# Horizontally_Mounted_Lighthouse_V16.net
KiCad netlist of a schematic drawn in EAGLE
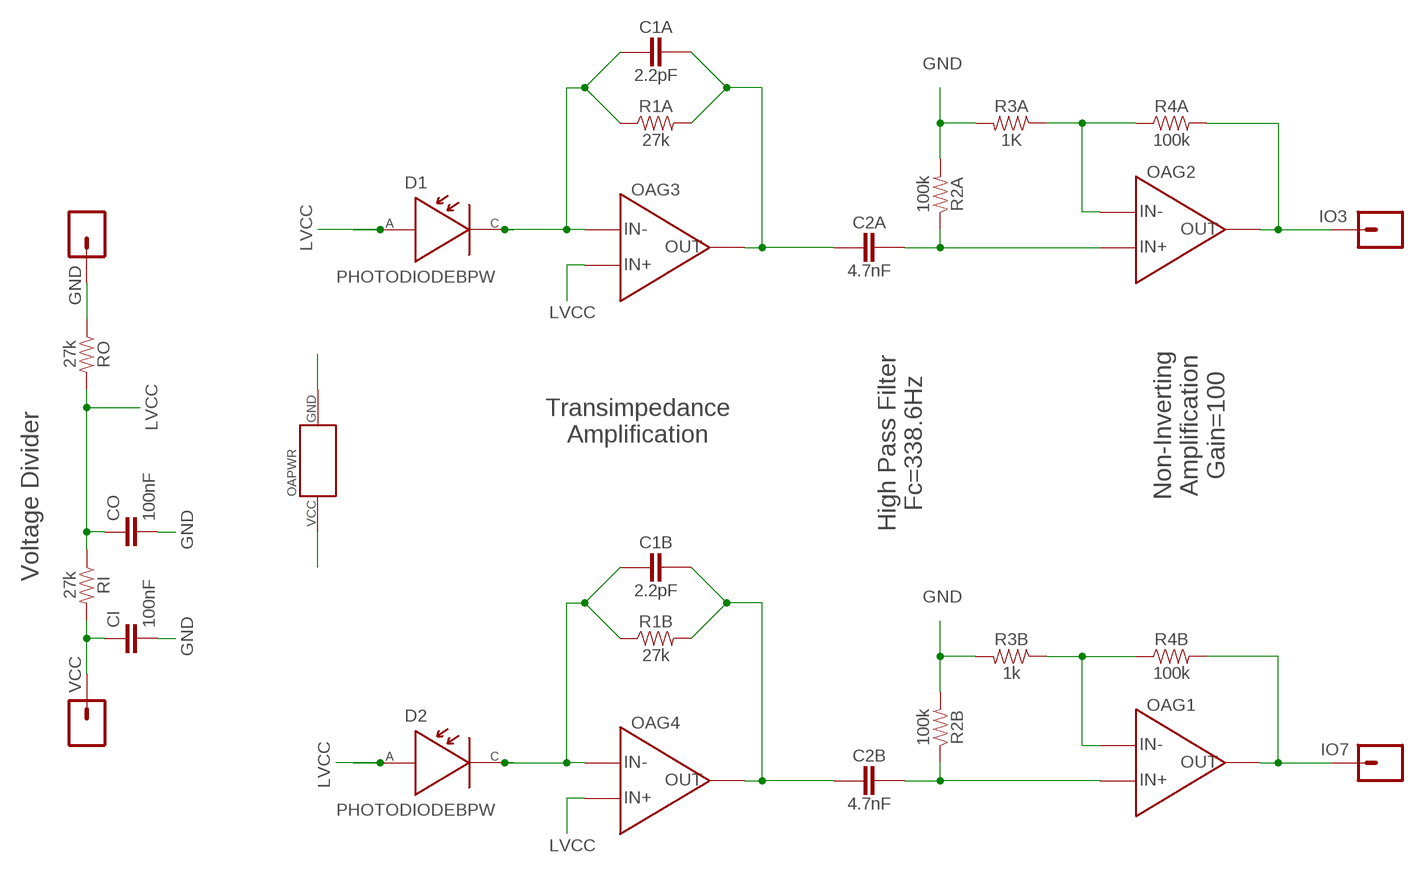
[diagram p0: schematic, sheet 1]

(export (version "E")
  (design (tool "Eeschema 10.0.6"))
  (components
    (comp (ref "C1A")
      (value "2.2pF")
      (footprint "eagle-import:PASSIVE-0603")
      (libsource (lib "eagle-import") (part "CAPACITOR"))
    )
    (comp (ref "C1B")
      (value "2.2pF")
      (footprint "eagle-import:PASSIVE-0603")
      (libsource (lib "eagle-import") (part "CAPACITOR"))
    )
    (comp (ref "C2A")
      (value "4.7nF")
      (footprint "eagle-import:PASSIVE-0603")
      (libsource (lib "eagle-import") (part "CAPACITOR"))
    )
    (comp (ref "C2B")
      (value "4.7nF")
      (footprint "eagle-import:PASSIVE-0603")
      (libsource (lib "eagle-import") (part "CAPACITOR"))
    )
    (comp (ref "CI")
      (value "100nF")
      (footprint "eagle-import:0603")
      (libsource (lib "eagle-import") (part "4.7PF-0603-50V-5%"))
    )
    (comp (ref "CO")
      (value "100nF")
      (footprint "eagle-import:0603")
      (libsource (lib "eagle-import") (part "4.7PF-0603-50V-5%"))
    )
    (comp (ref "D1")
      (value "PHOTODIODEBPW")
      (footprint "eagle-import:BPW34_BP104_SMD")
      (libsource (lib "eagle-import") (part "PHOTODIODEBPW"))
    )
    (comp (ref "D2")
      (value "PHOTODIODEBPW")
      (footprint "eagle-import:BPW34_BP104_SMD")
      (libsource (lib "eagle-import") (part "PHOTODIODEBPW"))
    )
    (comp (ref "GND")
      (value "CONN_01PTH_NO_SILK_YES_STOP")
      (footprint "eagle-import:1X01_NO_SILK")
      (libsource (lib "eagle-import") (part "CONN_01PTH_NO_SILK_YES_STOP"))
    )
    (comp (ref "IO3")
      (value "CONN_01PTH_NO_SILK_YES_STOP")
      (footprint "eagle-import:1X01_NO_SILK")
      (libsource (lib "eagle-import") (part "CONN_01PTH_NO_SILK_YES_STOP"))
    )
    (comp (ref "IO7")
      (value "CONN_01PTH_NO_SILK_YES_STOP")
      (footprint "eagle-import:1X01_NO_SILK")
      (libsource (lib "eagle-import") (part "CONN_01PTH_NO_SILK_YES_STOP"))
    )
    (comp (ref "OA")
      (value "TLV2464IDM")
      (footprint "eagle-import:D14-M")
      (libsource (lib "eagle-import") (part "TLV2464IDM"))
    )
    (comp (ref "R1A")
      (value "27k")
      (footprint "eagle-import:PASSIVE-0603")
      (libsource (lib "eagle-import") (part "RESISTOR"))
    )
    (comp (ref "R1B")
      (value "27k")
      (footprint "eagle-import:PASSIVE-0603")
      (libsource (lib "eagle-import") (part "RESISTOR"))
    )
    (comp (ref "R2A")
      (value "100k")
      (footprint "eagle-import:PASSIVE-0603")
      (libsource (lib "eagle-import") (part "RESISTOR"))
    )
    (comp (ref "R2B")
      (value "100k")
      (footprint "eagle-import:PASSIVE-0603")
      (libsource (lib "eagle-import") (part "RESISTOR"))
    )
    (comp (ref "R3A")
      (value "1K")
      (footprint "eagle-import:PASSIVE-0603")
      (libsource (lib "eagle-import") (part "RESISTOR"))
    )
    (comp (ref "R3B")
      (value "1k")
      (footprint "eagle-import:PASSIVE-0603")
      (libsource (lib "eagle-import") (part "RESISTOR"))
    )
    (comp (ref "R4A")
      (value "100k")
      (footprint "eagle-import:PASSIVE-0603")
      (libsource (lib "eagle-import") (part "RESISTOR"))
    )
    (comp (ref "R4B")
      (value "100k")
      (footprint "eagle-import:PASSIVE-0603")
      (libsource (lib "eagle-import") (part "RESISTOR"))
    )
    (comp (ref "RI")
      (value "27k")
      (footprint "eagle-import:0603")
      (libsource (lib "eagle-import") (part "100KOHM-0603-1/10W-1%"))
    )
    (comp (ref "RO")
      (value "27k")
      (footprint "eagle-import:0603")
      (libsource (lib "eagle-import") (part "100KOHM-0603-1/10W-1%"))
    )
    (comp (ref "VCC")
      (value "CONN_01PTH_NO_SILK_YES_STOP")
      (footprint "eagle-import:1X01_NO_SILK")
      (libsource (lib "eagle-import") (part "CONN_01PTH_NO_SILK_YES_STOP"))
    )
  )
  (nets
    (net (code "1") (name "/GND") (class "Default")
      (node (ref "CI") (pin "2") (pinfunction "2_2") (pintype "passive"))
      (node (ref "CO") (pin "2") (pinfunction "2_2") (pintype "passive"))
      (node (ref "GND") (pin "1") (pinfunction "1_1") (pintype "passive"))
      (node (ref "OA") (pin "11") (pinfunction "GND_11") (pintype "bidirectional"))
      (node (ref "R2A") (pin "2") (pinfunction "2_2") (pintype "passive"))
      (node (ref "R2B") (pin "2") (pinfunction "2_2") (pintype "passive"))
      (node (ref "R3A") (pin "2") (pinfunction "2_2") (pintype "passive"))
      (node (ref "R3B") (pin "2") (pinfunction "2_2") (pintype "passive"))
      (node (ref "RO") (pin "1") (pinfunction "1_1") (pintype "passive"))
    )
    (net (code "2") (name "/IO3") (class "Default")
      (node (ref "IO3") (pin "1") (pinfunction "1_1") (pintype "passive"))
      (node (ref "OA") (pin "7") (pinfunction "OUT_7") (pintype "bidirectional"))
      (node (ref "R4A") (pin "2") (pinfunction "2_2") (pintype "passive"))
    )
    (net (code "3") (name "/IO7") (class "Default")
      (node (ref "IO7") (pin "1") (pinfunction "1_1") (pintype "passive"))
      (node (ref "OA") (pin "1") (pinfunction "OUT_1") (pintype "bidirectional"))
      (node (ref "R4B") (pin "2") (pinfunction "2_2") (pintype "passive"))
    )
    (net (code "4") (name "/LVCC") (class "Default")
      (node (ref "CO") (pin "1") (pinfunction "1_1") (pintype "passive"))
      (node (ref "D1") (pin "ANODE") (pinfunction "ANODE_ANODE") (pintype "bidirectional"))
      (node (ref "D2") (pin "ANODE") (pinfunction "ANODE_ANODE") (pintype "bidirectional"))
      (node (ref "OA") (pin "10") (pinfunction "IN+_10") (pintype "bidirectional"))
      (node (ref "OA") (pin "12") (pinfunction "IN+_12") (pintype "bidirectional"))
      (node (ref "RI") (pin "1") (pinfunction "1_1") (pintype "passive"))
      (node (ref "RO") (pin "2") (pinfunction "2_2") (pintype "passive"))
    )
    (net (code "5") (name "/VCC") (class "Default")
      (node (ref "CI") (pin "1") (pinfunction "1_1") (pintype "passive"))
      (node (ref "OA") (pin "4") (pinfunction "VCC_4") (pintype "bidirectional"))
      (node (ref "RI") (pin "2") (pinfunction "2_2") (pintype "passive"))
      (node (ref "VCC") (pin "1") (pinfunction "1_1") (pintype "passive"))
    )
    (net (code "6") (name "Net-(OAA-IN+)") (class "Default")
      (node (ref "C2B") (pin "2") (pinfunction "2_2") (pintype "passive"))
      (node (ref "OA") (pin "3") (pinfunction "IN+_3") (pintype "bidirectional"))
      (node (ref "R2B") (pin "1") (pinfunction "1_1") (pintype "passive"))
    )
    (net (code "7") (name "Net-(OAA-IN-)") (class "Default")
      (node (ref "OA") (pin "2") (pinfunction "IN-_2") (pintype "bidirectional"))
      (node (ref "R3B") (pin "1") (pinfunction "1_1") (pintype "passive"))
      (node (ref "R4B") (pin "1") (pinfunction "1_1") (pintype "passive"))
    )
    (net (code "8") (name "Net-(OAB-IN+)") (class "Default")
      (node (ref "C2A") (pin "2") (pinfunction "2_2") (pintype "passive"))
      (node (ref "OA") (pin "5") (pinfunction "IN+_5") (pintype "bidirectional"))
      (node (ref "R2A") (pin "1") (pinfunction "1_1") (pintype "passive"))
    )
    (net (code "9") (name "Net-(OAB-IN-)") (class "Default")
      (node (ref "OA") (pin "6") (pinfunction "IN-_6") (pintype "bidirectional"))
      (node (ref "R3A") (pin "1") (pinfunction "1_1") (pintype "passive"))
      (node (ref "R4A") (pin "1") (pinfunction "1_1") (pintype "passive"))
    )
    (net (code "10") (name "Net-(OAC-IN-)") (class "Default")
      (node (ref "C1A") (pin "1") (pinfunction "1_1") (pintype "passive"))
      (node (ref "D1") (pin "CATHODE") (pinfunction "CATHODE_CATHODE") (pintype "bidirectional"))
      (node (ref "OA") (pin "9") (pinfunction "IN-_9") (pintype "bidirectional"))
      (node (ref "R1A") (pin "1") (pinfunction "1_1") (pintype "passive"))
    )
    (net (code "11") (name "Net-(OAC-OUT)") (class "Default")
      (node (ref "C1A") (pin "2") (pinfunction "2_2") (pintype "passive"))
      (node (ref "C2A") (pin "1") (pinfunction "1_1") (pintype "passive"))
      (node (ref "OA") (pin "8") (pinfunction "OUT_8") (pintype "bidirectional"))
      (node (ref "R1A") (pin "2") (pinfunction "2_2") (pintype "passive"))
    )
    (net (code "12") (name "Net-(OAD-IN-)") (class "Default")
      (node (ref "C1B") (pin "1") (pinfunction "1_1") (pintype "passive"))
      (node (ref "D2") (pin "CATHODE") (pinfunction "CATHODE_CATHODE") (pintype "bidirectional"))
      (node (ref "OA") (pin "13") (pinfunction "IN-_13") (pintype "bidirectional"))
      (node (ref "R1B") (pin "1") (pinfunction "1_1") (pintype "passive"))
    )
    (net (code "13") (name "Net-(OAD-OUT)") (class "Default")
      (node (ref "C1B") (pin "2") (pinfunction "2_2") (pintype "passive"))
      (node (ref "C2B") (pin "1") (pinfunction "1_1") (pintype "passive"))
      (node (ref "OA") (pin "14") (pinfunction "OUT_14") (pintype "bidirectional"))
      (node (ref "R1B") (pin "2") (pinfunction "2_2") (pintype "passive"))
    )
  )
)
